# TemperatureSensor.net
KiCad netlist of a schematic drawn in Altium Designer
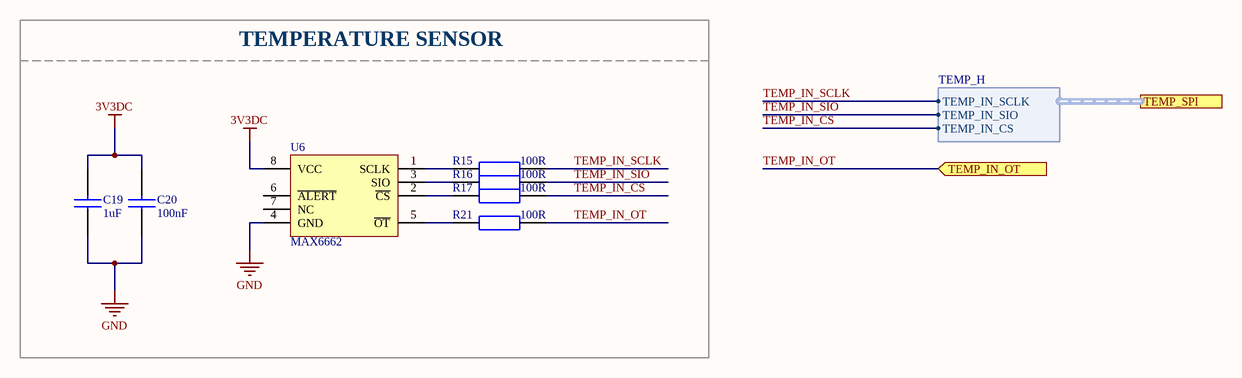
[diagram p0: TemperatureSensor.SchDoc]

(export (version "E")
  (design (tool "Eeschema 10.0.6"))
  (components
    (comp (ref "C19")
      (value "CL21B105KBFNNNE")
      (footprint "CAP_0805")
      (description "CAP CER 1uF %10 0805")
      (fields
        (field (name "MANUFACTURER") "Samsung")
        (field (name "TOLERANCE") "10%")
        (field (name "CAPACITANCE") "1uF")
        (field (name "DESIGNED BY") "BERK")
      )
      (libsource (lib "GuvenlikSistemi_Library") (part "CAP CER 1uF 0805"))
    )
    (comp (ref "C20")
      (value "CL21B104KBCNNNC")
      (footprint "CAP_0805")
      (description "CAP CER 100nF %10 0805")
      (fields
        (field (name "MANUFACTURER") "Samsung")
        (field (name "TOLERANCE") "10%")
        (field (name "CAPACITANCE") "100nF")
        (field (name "DESIGNED BY") "BERK")
      )
      (libsource (lib "GuvenlikSistemi_Library") (part "CAP CER 100nF 0805"))
    )
    (comp (ref "R15")
      (value "RC0603JR-07100RL")
      (footprint "RES_0603")
      (description "RES 100 %5 OHM 0603 SMD")
      (fields
        (field (name "MANUFACTURER") "Yageo")
        (field (name "TOLERANCE") "5%")
        (field (name "RESISTANCE") "100R")
        (field (name "DESIGNED BY") "BERK")
      )
      (libsource (lib "GuvenlikSistemi_Library") (part "RES 100 OHM 0603"))
    )
    (comp (ref "R16")
      (value "RC0603JR-07100RL")
      (footprint "RES_0603")
      (description "RES 100 %5 OHM 0603 SMD")
      (fields
        (field (name "MANUFACTURER") "Yageo")
        (field (name "TOLERANCE") "5%")
        (field (name "RESISTANCE") "100R")
        (field (name "DESIGNED BY") "BERK")
      )
      (libsource (lib "GuvenlikSistemi_Library") (part "RES 100 OHM 0603"))
    )
    (comp (ref "R17")
      (value "RC0603JR-07100RL")
      (footprint "RES_0603")
      (description "RES 100 %5 OHM 0603 SMD")
      (fields
        (field (name "MANUFACTURER") "Yageo")
        (field (name "TOLERANCE") "5%")
        (field (name "RESISTANCE") "100R")
        (field (name "DESIGNED BY") "BERK")
      )
      (libsource (lib "GuvenlikSistemi_Library") (part "RES 100 OHM 0603"))
    )
    (comp (ref "R21")
      (value "RC0603JR-07100RL")
      (footprint "RES_0603")
      (description "RES 100 %5 OHM 0603 SMD")
      (fields
        (field (name "MANUFACTURER") "Yageo")
        (field (name "TOLERANCE") "5%")
        (field (name "RESISTANCE") "100R")
        (field (name "DESIGNED BY") "BERK")
      )
      (libsource (lib "GuvenlikSistemi_Library") (part "RES 100 OHM 0603"))
    )
    (comp (ref "U6")
      (value "MAX6662")
      (footprint "SOIC8")
      (description "SENSOR TEMPERATURE SPI 8SOIC")
      (fields
        (field (name "MANUFACTURER") "Maxim")
        (field (name "MANUFACTURER PART NUMBER") "MAX6662MSA+")
        (field (name "DESIGNED BY") "BERK")
      )
      (libsource (lib "GuvenlikSistemi_Library") (part "MAX6662"))
    )
  )
  (nets
    (net (code "2") (name "/TEMP_IN_CS") (class "Default")
      (node (ref "R17") (pin "2") (pinfunction "2_2") (pintype "passive"))
    )
    (net (code "3") (name "/TEMP_IN_OT") (class "Default")
      (node (ref "R21") (pin "2") (pinfunction "2_2") (pintype "passive"))
    )
    (net (code "4") (name "/TEMP_IN_SCLK") (class "Default")
      (node (ref "R15") (pin "2") (pinfunction "2_2") (pintype "passive"))
    )
    (net (code "5") (name "/TEMP_IN_SIO") (class "Default")
      (node (ref "R16") (pin "2") (pinfunction "2_2") (pintype "passive"))
    )
    (net (code "7") (name "3V3DC") (class "Default")
      (node (ref "C19") (pin "2") (pinfunction "2_2") (pintype "passive"))
      (node (ref "C20") (pin "2") (pinfunction "2_2") (pintype "passive"))
      (node (ref "U6") (pin "8") (pinfunction "VCC_8") (pintype "passive"))
    )
    (net (code "8") (name "GND") (class "Default")
      (node (ref "C19") (pin "1") (pinfunction "1_1") (pintype "passive"))
      (node (ref "C20") (pin "1") (pinfunction "1_1") (pintype "passive"))
      (node (ref "U6") (pin "4") (pinfunction "GND_4") (pintype "passive"))
    )
    (net (code "9") (name "Net-(U6-SCLK)") (class "Default")
      (node (ref "R15") (pin "1") (pinfunction "1_1") (pintype "passive"))
      (node (ref "U6") (pin "1") (pinfunction "SCLK_1") (pintype "passive"))
    )
    (net (code "10") (name "Net-(U6-SIO)") (class "Default")
      (node (ref "R16") (pin "1") (pinfunction "1_1") (pintype "passive"))
      (node (ref "U6") (pin "3") (pinfunction "SIO_3") (pintype "passive"))
    )
    (net (code "11") (name "Net-(U6-~{CS})") (class "Default")
      (node (ref "R17") (pin "1") (pinfunction "1_1") (pintype "passive"))
      (node (ref "U6") (pin "2") (pinfunction "~{CS}_2") (pintype "passive"))
    )
    (net (code "12") (name "Net-(U6-~{OT})") (class "Default")
      (node (ref "R21") (pin "1") (pinfunction "1_1") (pintype "passive"))
      (node (ref "U6") (pin "5") (pinfunction "~{OT}_5") (pintype "passive"))
    )
    (net (code "13") (name "unconnected-(U6-NC-Pad7)") (class "Default")
      (node (ref "U6") (pin "7") (pinfunction "NC_7") (pintype "passive"))
    )
    (net (code "14") (name "unconnected-(U6-~{ALERT}-Pad6)") (class "Default")
      (node (ref "U6") (pin "6") (pinfunction "~{ALERT}_6") (pintype "passive"))
    )
  )
)
